# DSO_Counters.net
KiCad netlist of a schematic drawn in Altium Designer
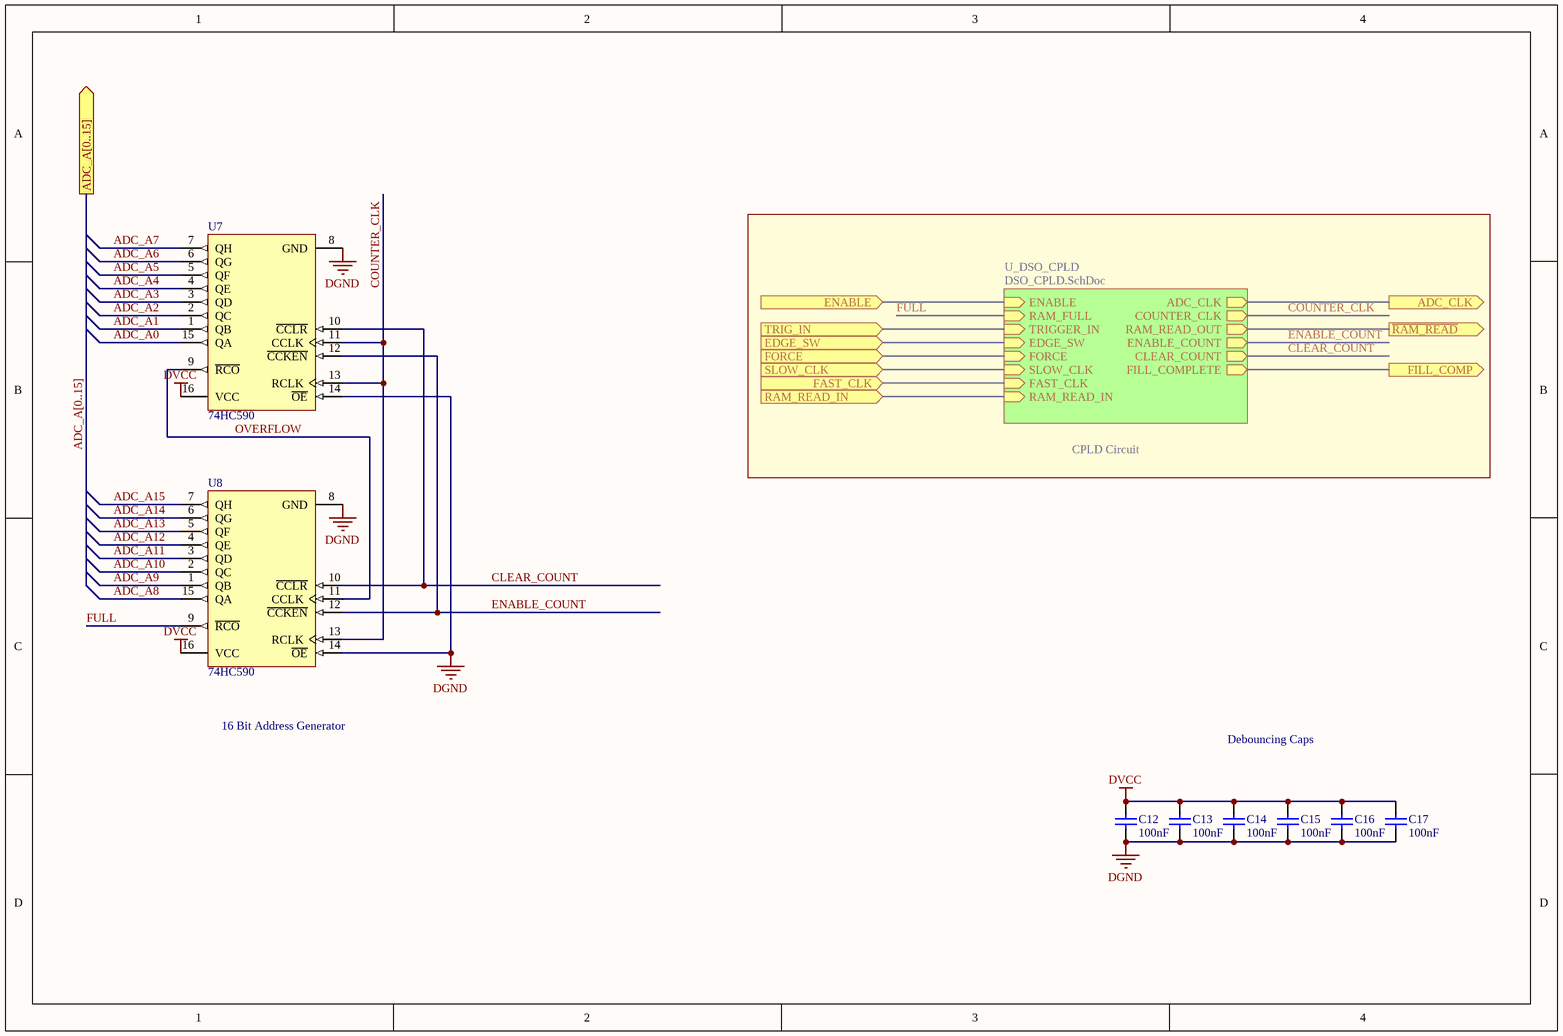
[diagram p0: DSO_Counters.SchDoc]

(export (version "E")
  (design (tool "Eeschema 10.0.6"))
  (components
    (comp (ref "C12")
      (value "100nF")
      (footprint "0805C")
      (description "Capacitor")
      (fields (field (name "REVIEWED BY") "RM - 2018/08/05"))
      (libsource (lib "DSO") (part "C"))
    )
    (comp (ref "C13")
      (value "100nF")
      (footprint "0805C")
      (description "Capacitor")
      (fields (field (name "REVIEWED BY") "RM - 2018/08/05"))
      (libsource (lib "DSO") (part "C"))
    )
    (comp (ref "C14")
      (value "100nF")
      (footprint "0805C")
      (description "Capacitor")
      (fields (field (name "REVIEWED BY") "RM - 2018/08/05"))
      (libsource (lib "DSO") (part "C"))
    )
    (comp (ref "C15")
      (value "100nF")
      (footprint "0805C")
      (description "Capacitor")
      (fields (field (name "REVIEWED BY") "RM - 2018/08/05"))
      (libsource (lib "DSO") (part "C"))
    )
    (comp (ref "C16")
      (value "100nF")
      (footprint "0805C")
      (description "Capacitor")
      (fields (field (name "REVIEWED BY") "RM - 2018/08/05"))
      (libsource (lib "DSO") (part "C"))
    )
    (comp (ref "C17")
      (value "100nF")
      (footprint "0805C")
      (description "Capacitor")
      (fields (field (name "REVIEWED BY") "RM - 2018/08/05"))
      (libsource (lib "DSO") (part "C"))
    )
    (comp (ref "U7")
      (value "74HC590")
      (footprint "SOIC-16")
      (description "8-Bit Binary Counter Register")
      (fields (field (name "REVIEWED BY") "RM - 2018/08/05"))
      (libsource (lib "DSO") (part "74HC590"))
    )
    (comp (ref "U8")
      (value "74HC590")
      (footprint "SOIC-16")
      (description "8-Bit Binary Counter Register")
      (fields (field (name "REVIEWED BY") "RM - 2018/08/05"))
      (libsource (lib "DSO") (part "74HC590"))
    )
  )
  (nets
    (net (code "1") (name "/ADC_A0") (class "Default")
      (node (ref "U7") (pin "15") (pinfunction "QA_15") (pintype "output"))
    )
    (net (code "2") (name "/ADC_A1") (class "Default")
      (node (ref "U7") (pin "1") (pinfunction "QB_1") (pintype "output"))
    )
    (net (code "3") (name "/ADC_A2") (class "Default")
      (node (ref "U7") (pin "2") (pinfunction "QC_2") (pintype "output"))
    )
    (net (code "4") (name "/ADC_A3") (class "Default")
      (node (ref "U7") (pin "3") (pinfunction "QD_3") (pintype "output"))
    )
    (net (code "5") (name "/ADC_A4") (class "Default")
      (node (ref "U7") (pin "4") (pinfunction "QE_4") (pintype "output"))
    )
    (net (code "6") (name "/ADC_A5") (class "Default")
      (node (ref "U7") (pin "5") (pinfunction "QF_5") (pintype "output"))
    )
    (net (code "7") (name "/ADC_A6") (class "Default")
      (node (ref "U7") (pin "6") (pinfunction "QG_6") (pintype "output"))
    )
    (net (code "8") (name "/ADC_A7") (class "Default")
      (node (ref "U7") (pin "7") (pinfunction "QH_7") (pintype "output"))
    )
    (net (code "9") (name "/ADC_A8") (class "Default")
      (node (ref "U8") (pin "15") (pinfunction "QA_15") (pintype "output"))
    )
    (net (code "10") (name "/ADC_A9") (class "Default")
      (node (ref "U8") (pin "1") (pinfunction "QB_1") (pintype "output"))
    )
    (net (code "11") (name "/ADC_A10") (class "Default")
      (node (ref "U8") (pin "2") (pinfunction "QC_2") (pintype "output"))
    )
    (net (code "12") (name "/ADC_A11") (class "Default")
      (node (ref "U8") (pin "3") (pinfunction "QD_3") (pintype "output"))
    )
    (net (code "13") (name "/ADC_A12") (class "Default")
      (node (ref "U8") (pin "4") (pinfunction "QE_4") (pintype "output"))
    )
    (net (code "14") (name "/ADC_A13") (class "Default")
      (node (ref "U8") (pin "5") (pinfunction "QF_5") (pintype "output"))
    )
    (net (code "15") (name "/ADC_A14") (class "Default")
      (node (ref "U8") (pin "6") (pinfunction "QG_6") (pintype "output"))
    )
    (net (code "16") (name "/ADC_A15") (class "Default")
      (node (ref "U8") (pin "7") (pinfunction "QH_7") (pintype "output"))
    )
    (net (code "19") (name "/CLEAR_COUNT") (class "Default")
      (node (ref "U7") (pin "10") (pinfunction "~{CCLR}_10") (pintype "input"))
      (node (ref "U8") (pin "10") (pinfunction "~{CCLR}_10") (pintype "input"))
    )
    (net (code "20") (name "/COUNTER_CLK") (class "Default")
      (node (ref "U7") (pin "11") (pinfunction "CCLK_11") (pintype "input"))
      (node (ref "U7") (pin "13") (pinfunction "RCLK_13") (pintype "input"))
      (node (ref "U8") (pin "13") (pinfunction "RCLK_13") (pintype "input"))
    )
    (net (code "23") (name "/ENABLE_COUNT") (class "Default")
      (node (ref "U7") (pin "12") (pinfunction "~{CCKEN}_12") (pintype "input"))
      (node (ref "U8") (pin "12") (pinfunction "~{CCKEN}_12") (pintype "input"))
    )
    (net (code "27") (name "/FULL") (class "Default")
      (node (ref "U8") (pin "9") (pinfunction "~{RCO}_9") (pintype "output"))
    )
    (net (code "28") (name "/OVERFLOW") (class "Default")
      (node (ref "U7") (pin "9") (pinfunction "~{RCO}_9") (pintype "output"))
      (node (ref "U8") (pin "11") (pinfunction "CCLK_11") (pintype "input"))
    )
    (net (code "33") (name "DGND") (class "Default")
      (node (ref "C12") (pin "2") (pinfunction "2_2") (pintype "passive"))
      (node (ref "C13") (pin "2") (pinfunction "2_2") (pintype "passive"))
      (node (ref "C14") (pin "2") (pinfunction "2_2") (pintype "passive"))
      (node (ref "C15") (pin "2") (pinfunction "2_2") (pintype "passive"))
      (node (ref "C16") (pin "2") (pinfunction "2_2") (pintype "passive"))
      (node (ref "C17") (pin "2") (pinfunction "2_2") (pintype "passive"))
      (node (ref "U7") (pin "14") (pinfunction "~{OE}_14") (pintype "input"))
      (node (ref "U7") (pin "8") (pinfunction "GND_8") (pintype "power_in"))
      (node (ref "U8") (pin "14") (pinfunction "~{OE}_14") (pintype "input"))
      (node (ref "U8") (pin "8") (pinfunction "GND_8") (pintype "power_in"))
    )
    (net (code "34") (name "DVCC") (class "Default")
      (node (ref "C12") (pin "1") (pinfunction "1_1") (pintype "passive"))
      (node (ref "C13") (pin "1") (pinfunction "1_1") (pintype "passive"))
      (node (ref "C14") (pin "1") (pinfunction "1_1") (pintype "passive"))
      (node (ref "C15") (pin "1") (pinfunction "1_1") (pintype "passive"))
      (node (ref "C16") (pin "1") (pinfunction "1_1") (pintype "passive"))
      (node (ref "C17") (pin "1") (pinfunction "1_1") (pintype "passive"))
      (node (ref "U7") (pin "16") (pinfunction "VCC_16") (pintype "power_in"))
      (node (ref "U8") (pin "16") (pinfunction "VCC_16") (pintype "power_in"))
    )
  )
)
